# OSSIBeaconPA.net
KiCad netlist of a schematic drawn in EAGLE
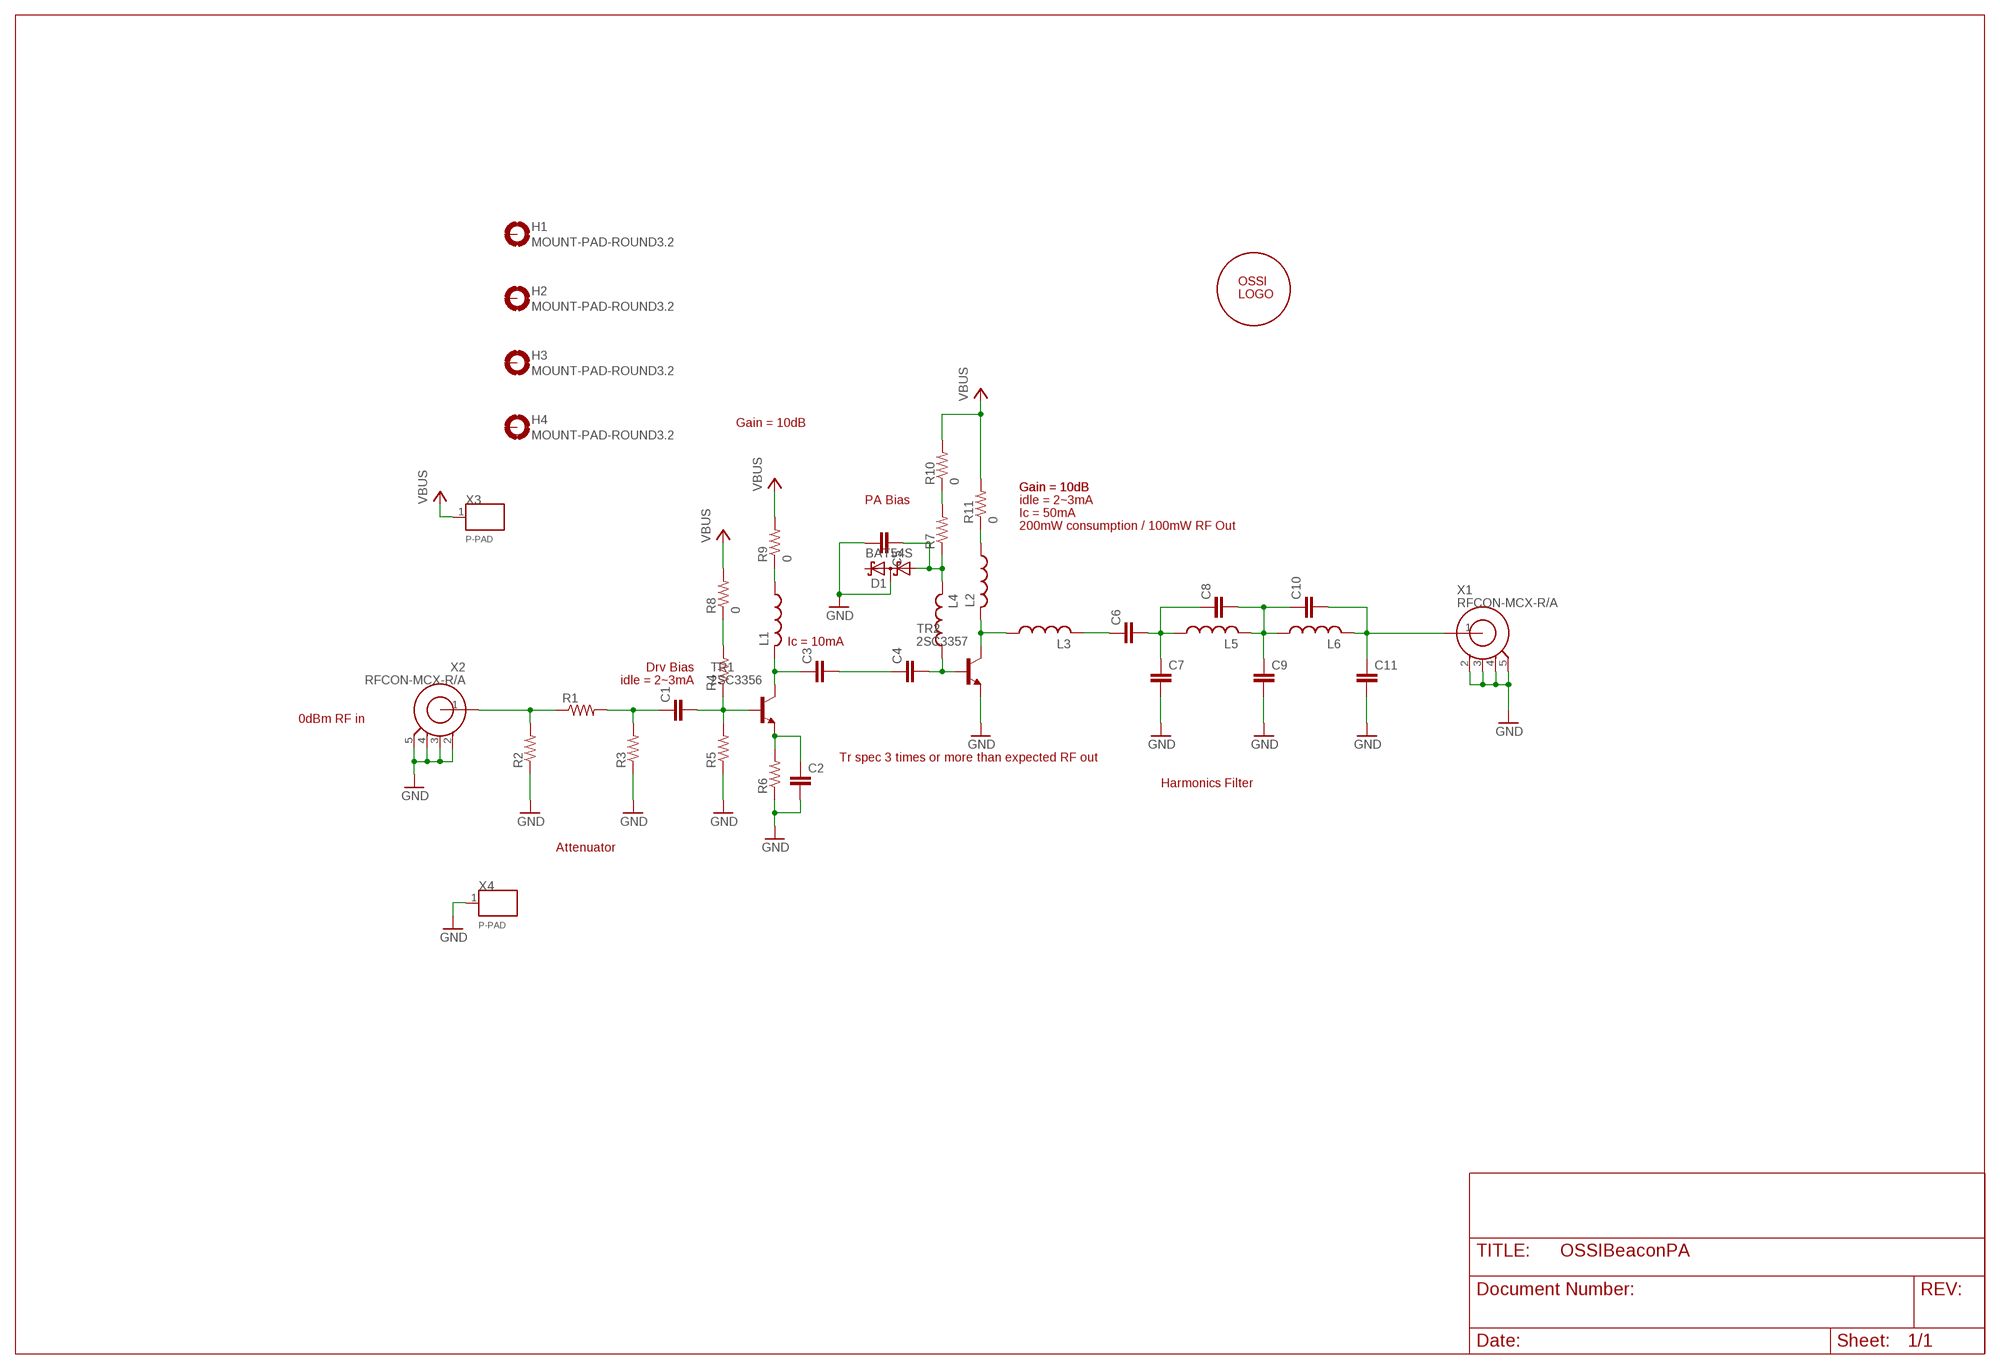
[diagram p0: schematic, sheet 1]

(export (version "E")
  (design (tool "Eeschema 10.0.6"))
  (components
    (comp (ref "C1")
      (value "C0603(1608)")
      (footprint "eagle-import:C0603(1608)")
      (libsource (lib "eagle-import") (part "C0603(1608)"))
    )
    (comp (ref "C2")
      (value "C0603(1608)")
      (footprint "eagle-import:C0603(1608)")
      (libsource (lib "eagle-import") (part "C0603(1608)"))
    )
    (comp (ref "C3")
      (value "C0603(1608)")
      (footprint "eagle-import:C0603(1608)")
      (libsource (lib "eagle-import") (part "C0603(1608)"))
    )
    (comp (ref "C4")
      (value "C0603(1608)")
      (footprint "eagle-import:C0603(1608)")
      (libsource (lib "eagle-import") (part "C0603(1608)"))
    )
    (comp (ref "C5")
      (value "C0603(1608)")
      (footprint "eagle-import:C0603(1608)")
      (libsource (lib "eagle-import") (part "C0603(1608)"))
    )
    (comp (ref "C6")
      (value "C0603(1608)")
      (footprint "eagle-import:C0603(1608)")
      (libsource (lib "eagle-import") (part "C0603(1608)"))
    )
    (comp (ref "C7")
      (value "C0603(1608)")
      (footprint "eagle-import:C0603(1608)")
      (libsource (lib "eagle-import") (part "C0603(1608)"))
    )
    (comp (ref "C8")
      (value "C0603(1608)")
      (footprint "eagle-import:C0603(1608)")
      (libsource (lib "eagle-import") (part "C0603(1608)"))
    )
    (comp (ref "C9")
      (value "C0603(1608)")
      (footprint "eagle-import:C0603(1608)")
      (libsource (lib "eagle-import") (part "C0603(1608)"))
    )
    (comp (ref "C10")
      (value "C0603(1608)")
      (footprint "eagle-import:C0603(1608)")
      (libsource (lib "eagle-import") (part "C0603(1608)"))
    )
    (comp (ref "C11")
      (value "C0603(1608)")
      (footprint "eagle-import:C0603(1608)")
      (libsource (lib "eagle-import") (part "C0603(1608)"))
    )
    (comp (ref "D1")
      (value "BAT54S")
      (footprint "eagle-import:SOT23")
      (libsource (lib "eagle-import") (part "BAT54S"))
    )
    (comp (ref "H1")
      (value "MOUNT-PAD-ROUND3.2")
      (footprint "eagle-import:3.2-PAD-ROUND")
      (libsource (lib "eagle-import") (part "MOUNT-PAD-ROUND3.2"))
    )
    (comp (ref "H2")
      (value "MOUNT-PAD-ROUND3.2")
      (footprint "eagle-import:3.2-PAD-ROUND")
      (libsource (lib "eagle-import") (part "MOUNT-PAD-ROUND3.2"))
    )
    (comp (ref "H3")
      (value "MOUNT-PAD-ROUND3.2")
      (footprint "eagle-import:3.2-PAD-ROUND")
      (libsource (lib "eagle-import") (part "MOUNT-PAD-ROUND3.2"))
    )
    (comp (ref "H4")
      (value "MOUNT-PAD-ROUND3.2")
      (footprint "eagle-import:3.2-PAD-ROUND")
      (libsource (lib "eagle-import") (part "MOUNT-PAD-ROUND3.2"))
    )
    (comp (ref "L1")
      (value "L1008(2502)")
      (footprint "eagle-import:L1008(2520)")
      (libsource (lib "eagle-import") (part "L1008(2502)"))
    )
    (comp (ref "L2")
      (value "L1008(2502)")
      (footprint "eagle-import:L1008(2520)")
      (libsource (lib "eagle-import") (part "L1008(2502)"))
    )
    (comp (ref "L3")
      (value "L0603(1608)")
      (footprint "eagle-import:L0603(1608)")
      (libsource (lib "eagle-import") (part "L0603(1608)"))
    )
    (comp (ref "L4")
      (value "L0603(1608)")
      (footprint "eagle-import:L0603(1608)")
      (libsource (lib "eagle-import") (part "L0603(1608)"))
    )
    (comp (ref "L5")
      (value "L0603(1608)")
      (footprint "eagle-import:L0603(1608)")
      (libsource (lib "eagle-import") (part "L0603(1608)"))
    )
    (comp (ref "L6")
      (value "L0603(1608)")
      (footprint "eagle-import:L0603(1608)")
      (libsource (lib "eagle-import") (part "L0603(1608)"))
    )
    (comp (ref "R1")
      (value "R0603(1608)")
      (footprint "eagle-import:R0603(1608)")
      (libsource (lib "eagle-import") (part "R0603(1608)"))
    )
    (comp (ref "R2")
      (value "R0603(1608)")
      (footprint "eagle-import:R0603(1608)")
      (libsource (lib "eagle-import") (part "R0603(1608)"))
    )
    (comp (ref "R3")
      (value "R0603(1608)")
      (footprint "eagle-import:R0603(1608)")
      (libsource (lib "eagle-import") (part "R0603(1608)"))
    )
    (comp (ref "R4")
      (value "R0603(1608)")
      (footprint "eagle-import:R0603(1608)")
      (libsource (lib "eagle-import") (part "R0603(1608)"))
    )
    (comp (ref "R5")
      (value "R0603(1608)")
      (footprint "eagle-import:R0603(1608)")
      (libsource (lib "eagle-import") (part "R0603(1608)"))
    )
    (comp (ref "R6")
      (value "R0603(1608)")
      (footprint "eagle-import:R0603(1608)")
      (libsource (lib "eagle-import") (part "R0603(1608)"))
    )
    (comp (ref "R7")
      (value "R0603(1608)")
      (footprint "eagle-import:R0603(1608)")
      (libsource (lib "eagle-import") (part "R0603(1608)"))
    )
    (comp (ref "R8")
      (value "0")
      (footprint "eagle-import:R0603(1608)")
      (libsource (lib "eagle-import") (part "R0603(1608)"))
    )
    (comp (ref "R9")
      (value "0")
      (footprint "eagle-import:R0603(1608)")
      (libsource (lib "eagle-import") (part "R0603(1608)"))
    )
    (comp (ref "R10")
      (value "0")
      (footprint "eagle-import:R0603(1608)")
      (libsource (lib "eagle-import") (part "R0603(1608)"))
    )
    (comp (ref "R11")
      (value "0")
      (footprint "eagle-import:R0603(1608)")
      (libsource (lib "eagle-import") (part "R0603(1608)"))
    )
    (comp (ref "TR1")
      (value "2SC3356")
      (footprint "eagle-import:SOT23-BEC")
      (libsource (lib "eagle-import") (part "2SC3356"))
    )
    (comp (ref "TR2")
      (value "2SC3357")
      (footprint "eagle-import:SOT89-R")
      (libsource (lib "eagle-import") (part "2SC3357"))
    )
    (comp (ref "U$1")
      (value "OSSILOGO")
      (footprint "eagle-import:OSSILOGORECT1005")
      (libsource (lib "eagle-import") (part "OSSILOGO"))
    )
    (comp (ref "X1")
      (value "RFCON-MCX-R/A")
      (footprint "eagle-import:MCX-R_A")
      (libsource (lib "eagle-import") (part "RFCON-MCX-R/A"))
    )
    (comp (ref "X2")
      (value "RFCON-MCX-R/A")
      (footprint "eagle-import:MCX-R_A")
      (libsource (lib "eagle-import") (part "RFCON-MCX-R/A"))
    )
    (comp (ref "X3")
      (value "P-PAD")
      (footprint "eagle-import:P-PAD")
      (libsource (lib "eagle-import") (part "P-PAD"))
    )
    (comp (ref "X4")
      (value "P-PAD")
      (footprint "eagle-import:P-PAD")
      (libsource (lib "eagle-import") (part "P-PAD"))
    )
  )
  (nets
    (net (code "1") (name "GND") (class "Default")
      (node (ref "C11") (pin "2") (pinfunction "2_2") (pintype "passive"))
      (node (ref "C2") (pin "2") (pinfunction "2_2") (pintype "passive"))
      (node (ref "C5") (pin "2") (pinfunction "2_2") (pintype "passive"))
      (node (ref "C7") (pin "2") (pinfunction "2_2") (pintype "passive"))
      (node (ref "C9") (pin "2") (pinfunction "2_2") (pintype "passive"))
      (node (ref "D1") (pin "3") (pinfunction "C1A2_3") (pintype "passive"))
      (node (ref "R2") (pin "1") (pinfunction "1_1") (pintype "passive"))
      (node (ref "R3") (pin "1") (pinfunction "1_1") (pintype "passive"))
      (node (ref "R5") (pin "1") (pinfunction "1_1") (pintype "passive"))
      (node (ref "R6") (pin "1") (pinfunction "1_1") (pintype "passive"))
      (node (ref "TR2") (pin "E") (pinfunction "E_E") (pintype "passive"))
      (node (ref "X1") (pin "2") (pinfunction "2_2") (pintype "power_in"))
      (node (ref "X1") (pin "3") (pinfunction "3_3") (pintype "power_in"))
      (node (ref "X1") (pin "4") (pinfunction "4_4") (pintype "power_in"))
      (node (ref "X1") (pin "5") (pinfunction "5_5") (pintype "power_in"))
      (node (ref "X2") (pin "2") (pinfunction "2_2") (pintype "power_in"))
      (node (ref "X2") (pin "3") (pinfunction "3_3") (pintype "power_in"))
      (node (ref "X2") (pin "4") (pinfunction "4_4") (pintype "power_in"))
      (node (ref "X2") (pin "5") (pinfunction "5_5") (pintype "power_in"))
      (node (ref "X4") (pin "1") (pinfunction "P$1_1") (pintype "bidirectional"))
    )
    (net (code "2") (name "Net-(C1-Pad1)") (class "Default")
      (node (ref "C1") (pin "1") (pinfunction "1_1") (pintype "passive"))
      (node (ref "R1") (pin "2") (pinfunction "2_2") (pintype "passive"))
      (node (ref "R3") (pin "2") (pinfunction "2_2") (pintype "passive"))
    )
    (net (code "3") (name "Net-(C1-Pad2)") (class "Default")
      (node (ref "C1") (pin "2") (pinfunction "2_2") (pintype "passive"))
      (node (ref "R4") (pin "1") (pinfunction "1_1") (pintype "passive"))
      (node (ref "R5") (pin "2") (pinfunction "2_2") (pintype "passive"))
      (node (ref "TR1") (pin "B") (pinfunction "B_B") (pintype "passive"))
    )
    (net (code "4") (name "Net-(C2-Pad1)") (class "Default")
      (node (ref "C2") (pin "1") (pinfunction "1_1") (pintype "passive"))
      (node (ref "R6") (pin "2") (pinfunction "2_2") (pintype "passive"))
      (node (ref "TR1") (pin "E") (pinfunction "E_E") (pintype "passive"))
    )
    (net (code "5") (name "Net-(C3-Pad2)") (class "Default")
      (node (ref "C3") (pin "2") (pinfunction "2_2") (pintype "passive"))
      (node (ref "C4") (pin "1") (pinfunction "1_1") (pintype "passive"))
    )
    (net (code "6") (name "Net-(C4-Pad2)") (class "Default")
      (node (ref "C4") (pin "2") (pinfunction "2_2") (pintype "passive"))
      (node (ref "L4") (pin "1") (pinfunction "1_1") (pintype "passive"))
      (node (ref "TR2") (pin "B") (pinfunction "B_B") (pintype "passive"))
    )
    (net (code "7") (name "Net-(C6-Pad1)") (class "Default")
      (node (ref "C6") (pin "1") (pinfunction "1_1") (pintype "passive"))
      (node (ref "L3") (pin "2") (pinfunction "2_2") (pintype "passive"))
    )
    (net (code "8") (name "Net-(C6-Pad2)") (class "Default")
      (node (ref "C6") (pin "2") (pinfunction "2_2") (pintype "passive"))
      (node (ref "C7") (pin "1") (pinfunction "1_1") (pintype "passive"))
      (node (ref "C8") (pin "1") (pinfunction "1_1") (pintype "passive"))
      (node (ref "L5") (pin "1") (pinfunction "1_1") (pintype "passive"))
    )
    (net (code "9") (name "Net-(C10-Pad1)") (class "Default")
      (node (ref "C10") (pin "1") (pinfunction "1_1") (pintype "passive"))
      (node (ref "C8") (pin "2") (pinfunction "2_2") (pintype "passive"))
      (node (ref "C9") (pin "1") (pinfunction "1_1") (pintype "passive"))
      (node (ref "L5") (pin "2") (pinfunction "2_2") (pintype "passive"))
      (node (ref "L6") (pin "1") (pinfunction "1_1") (pintype "passive"))
    )
    (net (code "10") (name "Net-(C10-Pad2)") (class "Default")
      (node (ref "C10") (pin "2") (pinfunction "2_2") (pintype "passive"))
      (node (ref "C11") (pin "1") (pinfunction "1_1") (pintype "passive"))
      (node (ref "L6") (pin "2") (pinfunction "2_2") (pintype "passive"))
      (node (ref "X1") (pin "1") (pinfunction "1_1") (pintype "bidirectional"))
    )
    (net (code "11") (name "Net-(D1-A1)") (class "Default")
      (node (ref "C5") (pin "1") (pinfunction "1_1") (pintype "passive"))
      (node (ref "D1") (pin "1") (pinfunction "A1_1") (pintype "passive"))
      (node (ref "L4") (pin "2") (pinfunction "2_2") (pintype "passive"))
      (node (ref "R7") (pin "1") (pinfunction "1_1") (pintype "passive"))
    )
    (net (code "12") (name "Net-(L1-1)") (class "Default")
      (node (ref "L1") (pin "P$1") (pinfunction "1_P$1") (pintype "passive"))
      (node (ref "R9") (pin "1") (pinfunction "1_1") (pintype "passive"))
    )
    (net (code "13") (name "Net-(L1-2)") (class "Default")
      (node (ref "C3") (pin "1") (pinfunction "1_1") (pintype "passive"))
      (node (ref "L1") (pin "P$2") (pinfunction "2_P$2") (pintype "passive"))
      (node (ref "TR1") (pin "C") (pinfunction "C_C") (pintype "passive"))
    )
    (net (code "14") (name "Net-(L2-1)") (class "Default")
      (node (ref "L2") (pin "P$1") (pinfunction "1_P$1") (pintype "passive"))
      (node (ref "R11") (pin "1") (pinfunction "1_1") (pintype "passive"))
    )
    (net (code "15") (name "Net-(L2-2)") (class "Default")
      (node (ref "L2") (pin "P$2") (pinfunction "2_P$2") (pintype "passive"))
      (node (ref "L3") (pin "1") (pinfunction "1_1") (pintype "passive"))
      (node (ref "TR2") (pin "C") (pinfunction "C_C") (pintype "passive"))
    )
    (net (code "16") (name "Net-(R1-Pad1)") (class "Default")
      (node (ref "R1") (pin "1") (pinfunction "1_1") (pintype "passive"))
      (node (ref "R2") (pin "2") (pinfunction "2_2") (pintype "passive"))
      (node (ref "X2") (pin "1") (pinfunction "1_1") (pintype "bidirectional"))
    )
    (net (code "17") (name "Net-(R4-Pad2)") (class "Default")
      (node (ref "R4") (pin "2") (pinfunction "2_2") (pintype "passive"))
      (node (ref "R8") (pin "1") (pinfunction "1_1") (pintype "passive"))
    )
    (net (code "18") (name "Net-(R10-Pad1)") (class "Default")
      (node (ref "R10") (pin "1") (pinfunction "1_1") (pintype "passive"))
      (node (ref "R7") (pin "2") (pinfunction "2_2") (pintype "passive"))
    )
    (net (code "19") (name "VBUS") (class "Default")
      (node (ref "R10") (pin "2") (pinfunction "2_2") (pintype "passive"))
      (node (ref "R11") (pin "2") (pinfunction "2_2") (pintype "passive"))
      (node (ref "R8") (pin "2") (pinfunction "2_2") (pintype "passive"))
      (node (ref "R9") (pin "2") (pinfunction "2_2") (pintype "passive"))
      (node (ref "X3") (pin "1") (pinfunction "P$1_1") (pintype "bidirectional"))
    )
    (net (code "20") (name "unconnected-(D1-C2-Pad2)") (class "Default")
      (node (ref "D1") (pin "2") (pinfunction "C2_2") (pintype "passive"))
    )
    (net (code "21") (name "unconnected-(H1-MOUNT-PadB3,2)") (class "Default")
      (node (ref "H1") (pin "B3,2") (pinfunction "MOUNT_B3,2") (pintype "passive"))
    )
    (net (code "22") (name "unconnected-(H2-MOUNT-PadB3,2)") (class "Default")
      (node (ref "H2") (pin "B3,2") (pinfunction "MOUNT_B3,2") (pintype "passive"))
    )
    (net (code "23") (name "unconnected-(H3-MOUNT-PadB3,2)") (class "Default")
      (node (ref "H3") (pin "B3,2") (pinfunction "MOUNT_B3,2") (pintype "passive"))
    )
    (net (code "24") (name "unconnected-(H4-MOUNT-PadB3,2)") (class "Default")
      (node (ref "H4") (pin "B3,2") (pinfunction "MOUNT_B3,2") (pintype "passive"))
    )
  )
)
